# Pow-OR_v13-SFE.net
KiCad netlist of a schematic drawn in EAGLE
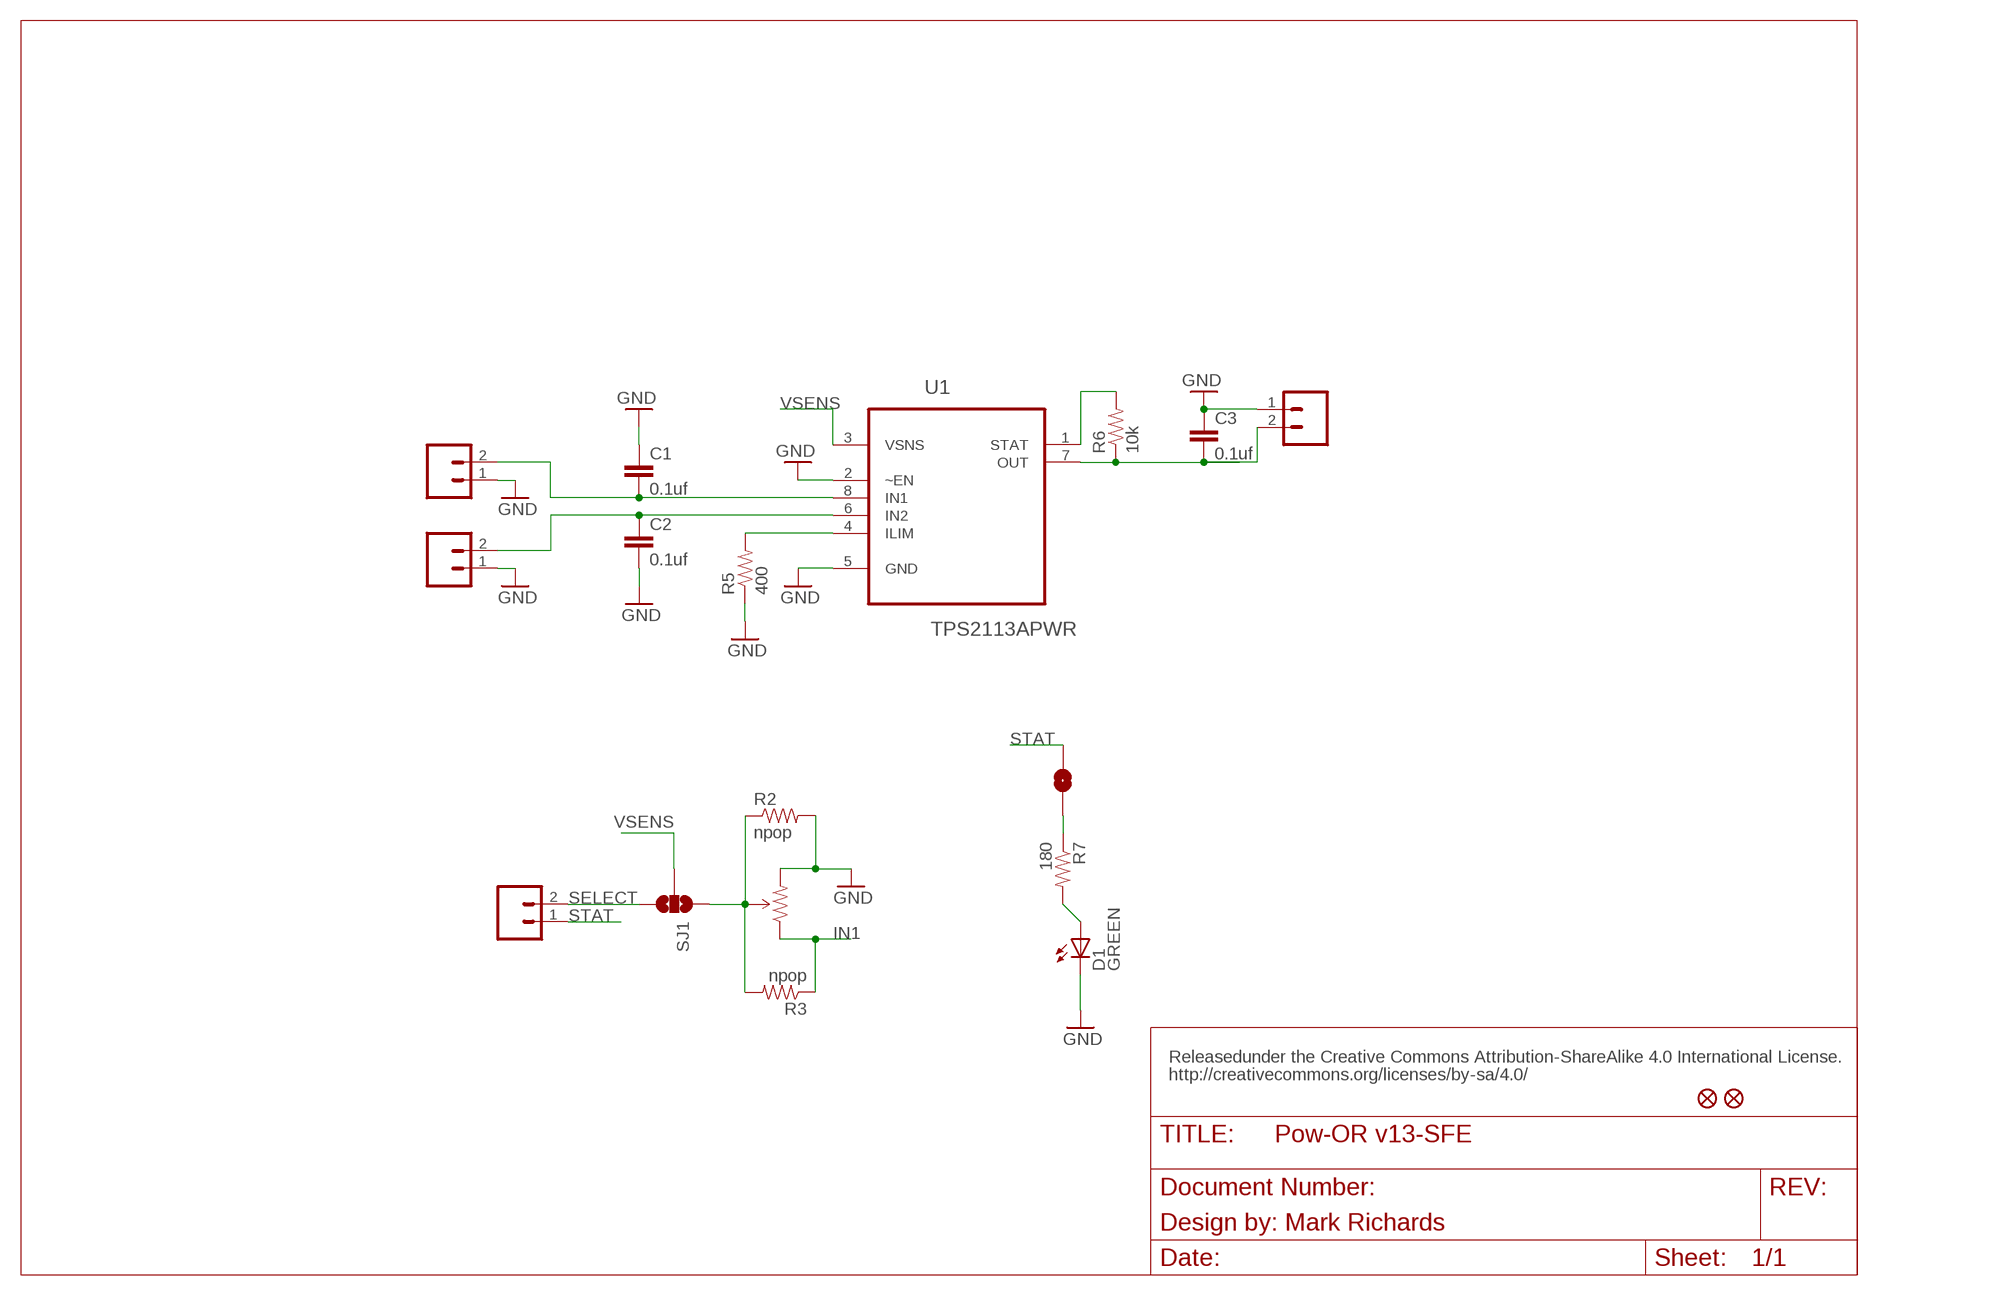
[diagram p0: schematic, sheet 1]

(export (version "E")
  (design (tool "Eeschema 10.0.6"))
  (components
    (comp (ref "C1")
      (value "0.1uf")
      (footprint "eagle-import:0603-CAP")
      (libsource (lib "eagle-import") (part "SparkFun-Passives_CAP0603-CAP"))
    )
    (comp (ref "C2")
      (value "0.1uf")
      (footprint "eagle-import:0603-CAP")
      (libsource (lib "eagle-import") (part "SparkFun-Passives_CAP0603-CAP"))
    )
    (comp (ref "C3")
      (value "0.1uf")
      (footprint "eagle-import:0603-CAP")
      (libsource (lib "eagle-import") (part "CAP0603-CAP"))
    )
    (comp (ref "D1")
      (value "GREEN")
      (footprint "eagle-import:LED-0603")
      (libsource (lib "eagle-import") (part "LED-GREEN0603"))
    )
    (comp (ref "FID1")
      (value "FIDUCIAL1X2")
      (footprint "eagle-import:FIDUCIAL-1X2")
      (libsource (lib "eagle-import") (part "FIDUCIAL1X2"))
    )
    (comp (ref "FID2")
      (value "FIDUCIAL1X2")
      (footprint "eagle-import:FIDUCIAL-1X2")
      (libsource (lib "eagle-import") (part "FIDUCIAL1X2"))
    )
    (comp (ref "JP3")
      (value "M021X02_NO_SILK")
      (footprint "eagle-import:1X02_NO_SILK")
      (libsource (lib "eagle-import") (part "M021X02_NO_SILK"))
    )
    (comp (ref "JP4")
      (value "M021X02_NO_SILK")
      (footprint "eagle-import:1X02_NO_SILK")
      (libsource (lib "eagle-import") (part "M021X02_NO_SILK"))
    )
    (comp (ref "JP5")
      (value "M021X02_NO_SILK")
      (footprint "eagle-import:1X02_NO_SILK")
      (libsource (lib "eagle-import") (part "M021X02_NO_SILK"))
    )
    (comp (ref "JP6")
      (value "M021X02_NO_SILK")
      (footprint "eagle-import:1X02_NO_SILK")
      (libsource (lib "eagle-import") (part "M021X02_NO_SILK"))
    )
    (comp (ref "R1")
      (value "TRIMPOT-PTH-KNOB")
      (footprint "eagle-import:3386U")
      (libsource (lib "eagle-import") (part "TRIMPOT-PTH-KNOB"))
    )
    (comp (ref "R2")
      (value "npop")
      (footprint "eagle-import:0603-RES")
      (libsource (lib "eagle-import") (part "RESISTOR0603"))
    )
    (comp (ref "R3")
      (value "npop")
      (footprint "eagle-import:0603-RES")
      (libsource (lib "eagle-import") (part "RESISTOR0603"))
    )
    (comp (ref "R5")
      (value "400")
      (footprint "eagle-import:0603-RES")
      (libsource (lib "eagle-import") (part "RESISTOR0603-RES"))
    )
    (comp (ref "R6")
      (value "10k")
      (footprint "eagle-import:0603-RES")
      (libsource (lib "eagle-import") (part "RESISTOR0603-RES"))
    )
    (comp (ref "R7")
      (value "180")
      (footprint "eagle-import:0603-RES")
      (libsource (lib "eagle-import") (part "RESISTOR0603-RES"))
    )
    (comp (ref "SJ1")
      (value "SOLDERJUMPER_2WAYPASTE1&2")
      (footprint "eagle-import:SJ_3_PASTE1&2")
      (libsource (lib "eagle-import") (part "SOLDERJUMPER_2WAYPASTE1&2"))
    )
    (comp (ref "SJ2")
      (value "SOLDERJUMPERNC2")
      (footprint "eagle-import:SJ_2S-NOTRACE")
      (libsource (lib "eagle-import") (part "SOLDERJUMPERNC2"))
    )
    (comp (ref "U1")
      (value "TPS2113APWR")
      (footprint "eagle-import:SOP65P640X120-8N")
      (libsource (lib "eagle-import") (part "TPS2113APWR"))
    )
  )
  (nets
    (net (code "1") (name "/IN1") (class "Default")
      (node (ref "C1") (pin "2") (pinfunction "2_2") (pintype "passive"))
      (node (ref "JP3") (pin "2") (pinfunction "2_2") (pintype "passive"))
      (node (ref "R1") (pin "1") (pinfunction "CCW_1") (pintype "passive"))
      (node (ref "R3") (pin "1") (pinfunction "1_1") (pintype "passive"))
      (node (ref "U1") (pin "8") (pinfunction "IN1_8") (pintype "input"))
    )
    (net (code "2") (name "/OUT") (class "Default")
      (node (ref "C3") (pin "2") (pinfunction "2_2") (pintype "passive"))
      (node (ref "JP6") (pin "2") (pinfunction "2_2") (pintype "passive"))
      (node (ref "R6") (pin "1") (pinfunction "1_1") (pintype "passive"))
      (node (ref "U1") (pin "7") (pinfunction "OUT_7") (pintype "output"))
    )
    (net (code "3") (name "/SELECT") (class "Default")
      (node (ref "JP5") (pin "2") (pinfunction "2_2") (pintype "passive"))
      (node (ref "SJ1") (pin "3") (pinfunction "3_3") (pintype "passive"))
    )
    (net (code "4") (name "/STAT") (class "Default")
      (node (ref "JP5") (pin "1") (pinfunction "1_1") (pintype "passive"))
      (node (ref "R6") (pin "2") (pinfunction "2_2") (pintype "passive"))
      (node (ref "SJ2") (pin "2") (pinfunction "2_2") (pintype "passive"))
      (node (ref "U1") (pin "1") (pinfunction "STAT_1") (pintype "output"))
    )
    (net (code "5") (name "/VSENS") (class "Default")
      (node (ref "SJ1") (pin "2") (pinfunction "2_2") (pintype "passive"))
      (node (ref "U1") (pin "3") (pinfunction "VSNS_3") (pintype "power_in"))
    )
    (net (code "6") (name "GND") (class "Default")
      (node (ref "C1") (pin "1") (pinfunction "1_1") (pintype "passive"))
      (node (ref "C2") (pin "2") (pinfunction "2_2") (pintype "passive"))
      (node (ref "C3") (pin "1") (pinfunction "1_1") (pintype "passive"))
      (node (ref "D1") (pin "C") (pinfunction "C_C") (pintype "passive"))
      (node (ref "JP3") (pin "1") (pinfunction "1_1") (pintype "passive"))
      (node (ref "JP4") (pin "1") (pinfunction "1_1") (pintype "passive"))
      (node (ref "JP6") (pin "1") (pinfunction "1_1") (pintype "passive"))
      (node (ref "R1") (pin "3") (pinfunction "CW_3") (pintype "passive"))
      (node (ref "R2") (pin "2") (pinfunction "2_2") (pintype "passive"))
      (node (ref "R5") (pin "1") (pinfunction "1_1") (pintype "passive"))
      (node (ref "U1") (pin "2") (pinfunction "~{EN}_2") (pintype "input"))
      (node (ref "U1") (pin "5") (pinfunction "GND_5") (pintype "passive"))
    )
    (net (code "7") (name "Net-(D1-PadA)") (class "Default")
      (node (ref "D1") (pin "A") (pinfunction "A_A") (pintype "passive"))
      (node (ref "R7") (pin "2") (pinfunction "2_2") (pintype "passive"))
    )
    (net (code "8") (name "Net-(R1-WIPER)") (class "Default")
      (node (ref "R1") (pin "2") (pinfunction "WIPER_2") (pintype "passive"))
      (node (ref "R2") (pin "1") (pinfunction "1_1") (pintype "passive"))
      (node (ref "R3") (pin "2") (pinfunction "2_2") (pintype "passive"))
      (node (ref "SJ1") (pin "1") (pinfunction "1_1") (pintype "passive"))
    )
    (net (code "9") (name "Net-(R7-Pad1)") (class "Default")
      (node (ref "R7") (pin "1") (pinfunction "1_1") (pintype "passive"))
      (node (ref "SJ2") (pin "1") (pinfunction "1_1") (pintype "passive"))
    )
    (net (code "10") (name "Net-(U1-ILIM)") (class "Default")
      (node (ref "R5") (pin "2") (pinfunction "2_2") (pintype "passive"))
      (node (ref "U1") (pin "4") (pinfunction "ILIM_4") (pintype "input"))
    )
    (net (code "11") (name "Net-(U1-IN2)") (class "Default")
      (node (ref "C2") (pin "1") (pinfunction "1_1") (pintype "passive"))
      (node (ref "JP4") (pin "2") (pinfunction "2_2") (pintype "passive"))
      (node (ref "U1") (pin "6") (pinfunction "IN2_6") (pintype "input"))
    )
  )
)
